# mapleCUx_large_177.net
KiCad netlist of a schematic drawn in EAGLE
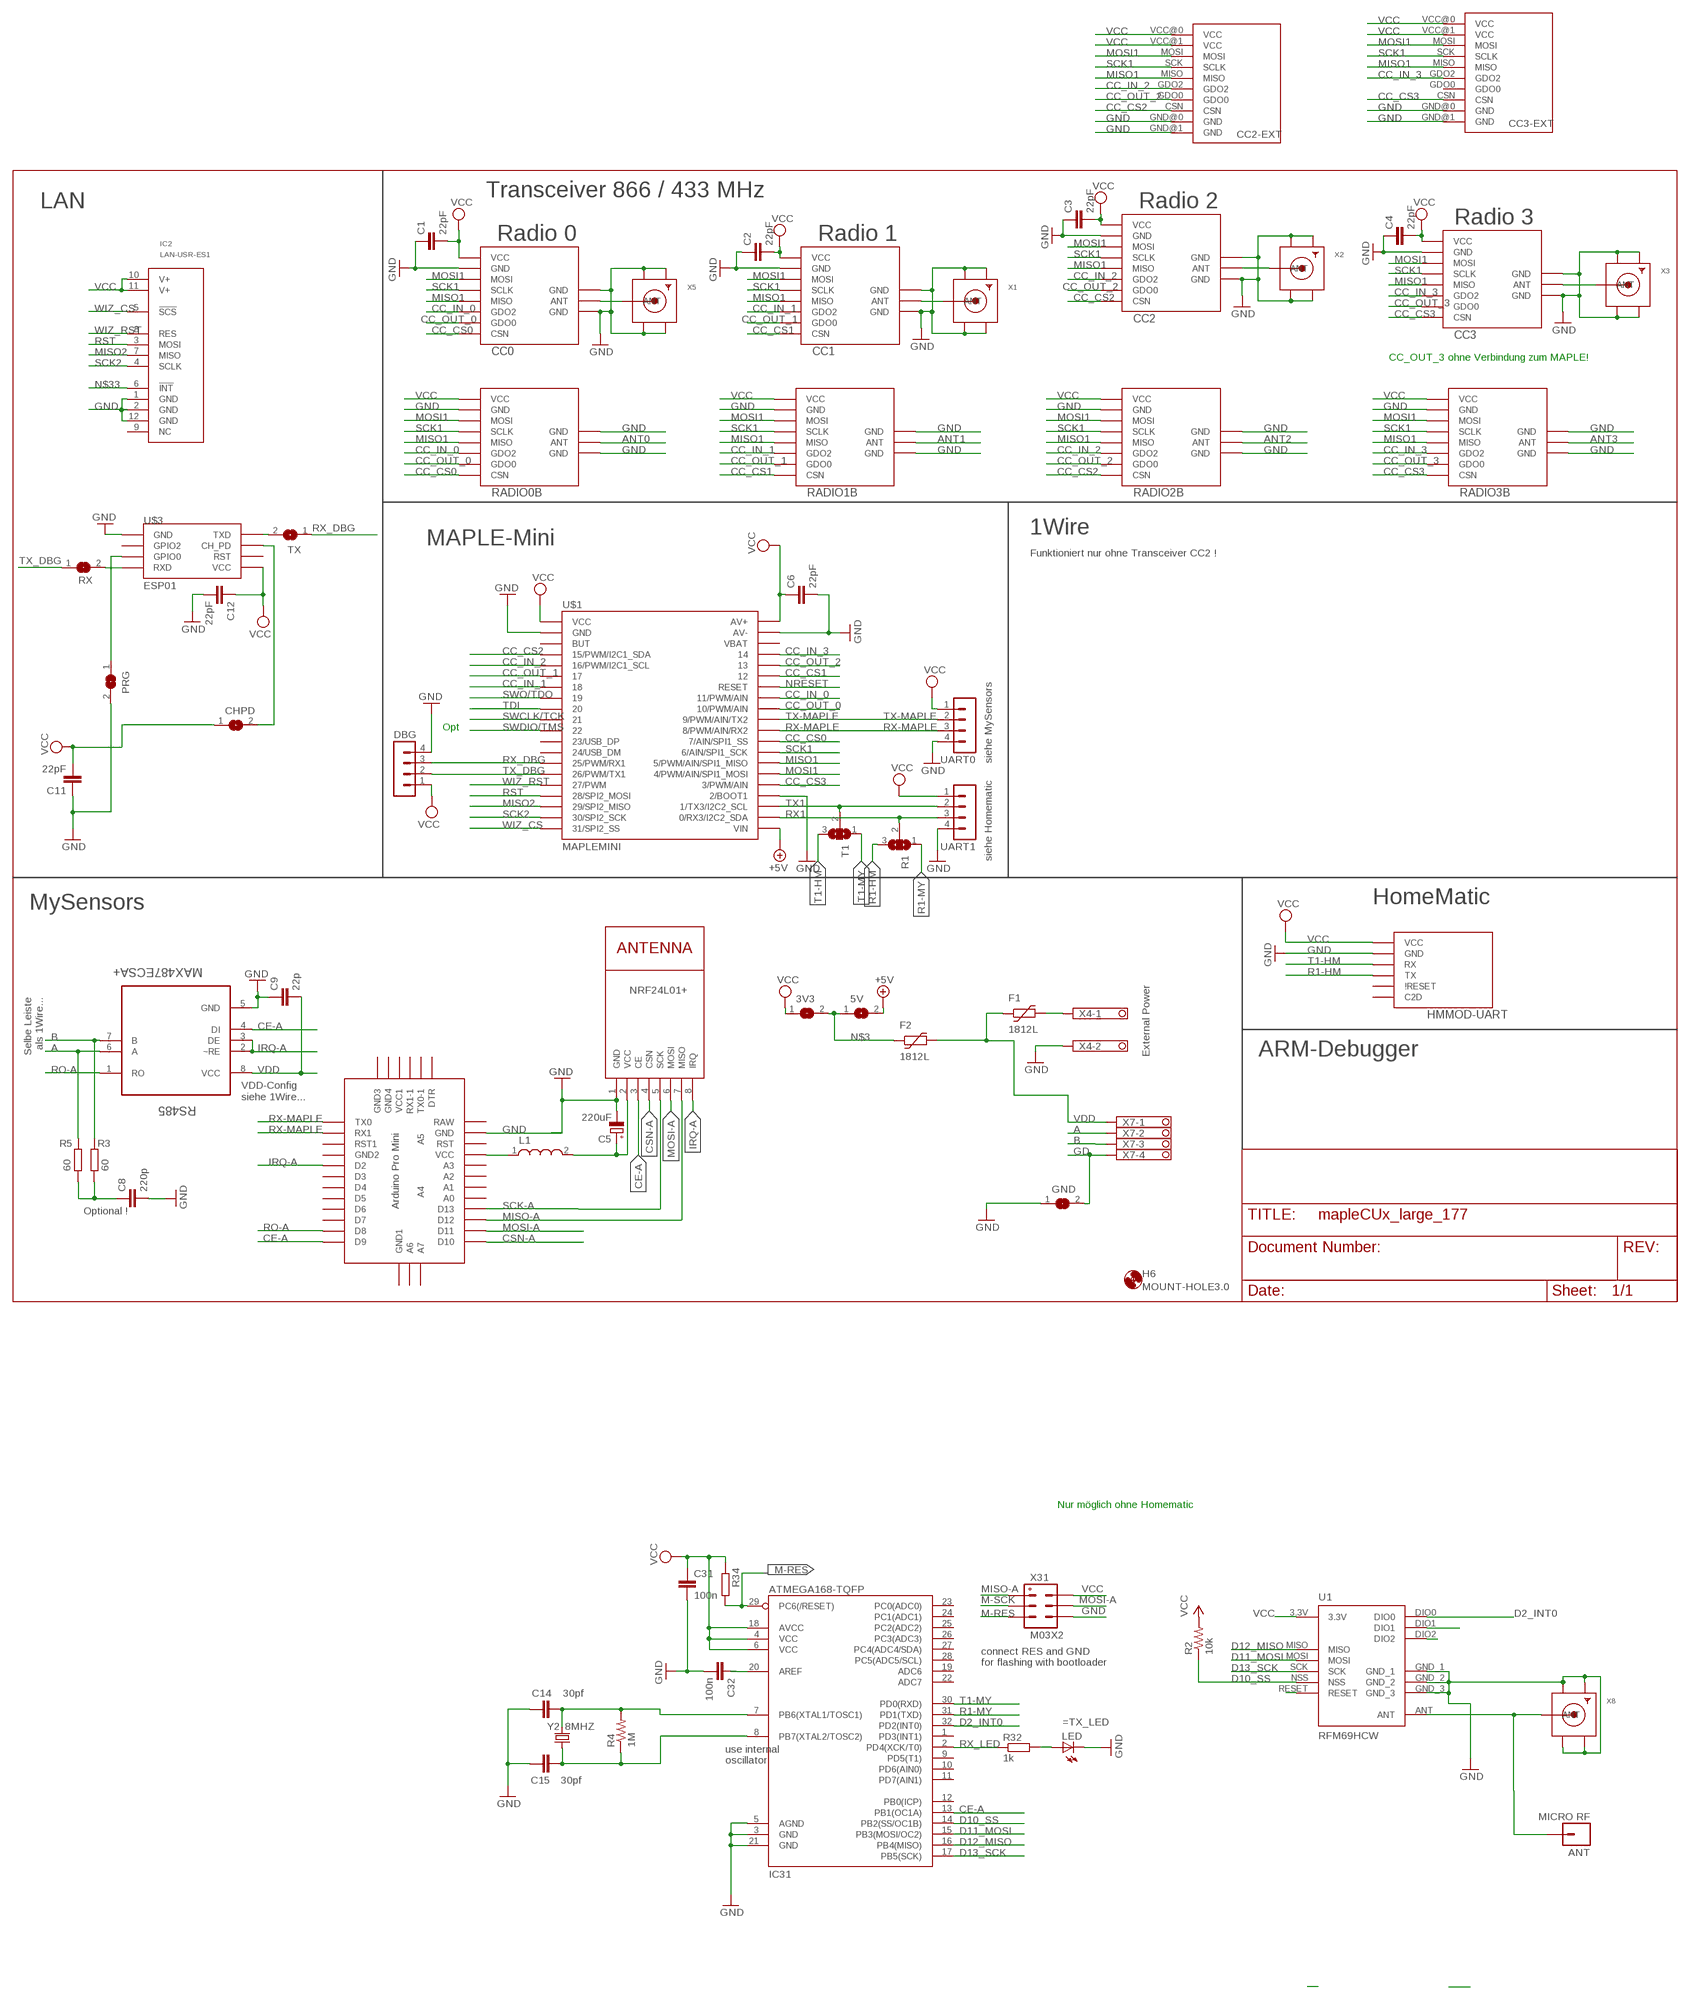
[diagram p0: schematic, sheet 1]

(export (version "E")
  (design (tool "Eeschema 10.0.6"))
  (components
    (comp (ref "3V3") (value "SJ") (footprint "eagle-import:SJ") (libsource (lib "eagle-import") (part "SJ")))
    (comp (ref "5V") (value "SJ") (footprint "eagle-import:SJ") (libsource (lib "eagle-import") (part "SJ")))
    (comp (ref "ANT")
      (value "MICRO RF")
      (footprint "eagle-import:1X01")
      (libsource (lib "eagle-import") (part "M01PTH"))
    )
    (comp (ref "C1")
      (value "22pF")
      (footprint "eagle-import:C0805")
      (libsource (lib "eagle-import") (part "C-EUC0805"))
    )
    (comp (ref "C2")
      (value "22pF")
      (footprint "eagle-import:C0805")
      (libsource (lib "eagle-import") (part "C-EUC0805"))
    )
    (comp (ref "C3")
      (value "22pF")
      (footprint "eagle-import:C0805")
      (libsource (lib "eagle-import") (part "C-EUC0805"))
    )
    (comp (ref "C4")
      (value "22pF")
      (footprint "eagle-import:C0805")
      (libsource (lib "eagle-import") (part "C-EUC0805"))
    )
    (comp (ref "C5")
      (value "220uF")
      (footprint "eagle-import:E5-8,5")
      (libsource (lib "eagle-import") (part "CPOL-EUE5-8.5"))
    )
    (comp (ref "C6")
      (value "22pF")
      (footprint "eagle-import:C0805")
      (libsource (lib "eagle-import") (part "C-EUC0805"))
    )
    (comp (ref "C8")
      (value "220p")
      (footprint "eagle-import:C0805")
      (libsource (lib "eagle-import") (part "C-EUC0805"))
    )
    (comp (ref "C9")
      (value "22p")
      (footprint "eagle-import:C0805")
      (libsource (lib "eagle-import") (part "C-EUC0805"))
    )
    (comp (ref "C11")
      (value "22pF")
      (footprint "eagle-import:C0805")
      (libsource (lib "eagle-import") (part "C-EUC0805"))
    )
    (comp (ref "C12")
      (value "22pF")
      (footprint "eagle-import:C0805")
      (libsource (lib "eagle-import") (part "C-EUC0805"))
    )
    (comp (ref "C14")
      (value "30pf")
      (footprint "eagle-import:0805")
      (libsource (lib "eagle-import") (part "CAP0805"))
    )
    (comp (ref "C15")
      (value "30pf")
      (footprint "eagle-import:0805")
      (libsource (lib "eagle-import") (part "CAP0805"))
    )
    (comp (ref "C31")
      (value "100n")
      (footprint "eagle-import:C0805")
      (libsource (lib "eagle-import") (part "C-EUC0805"))
    )
    (comp (ref "C32")
      (value "100n")
      (footprint "eagle-import:C0805")
      (libsource (lib "eagle-import") (part "C-EUC0805"))
    )
    (comp (ref "CC0")
      (value "CC1101")
      (footprint "eagle-import:CC1101_MODULE1_SMD")
      (libsource (lib "eagle-import") (part "wireless_CC1101_MODULE1SMD"))
    )
    (comp (ref "CC1")
      (value "CC1101_MODULE1SMD")
      (footprint "eagle-import:CC1101_MODULE1_SMD")
      (libsource (lib "eagle-import") (part "wireless_CC1101_MODULE1SMD"))
    )
    (comp (ref "CC2")
      (value "CC1101_MODULE1SMD")
      (footprint "eagle-import:CC1101_MODULE1_SMD")
      (libsource (lib "eagle-import") (part "wireless_CC1101_MODULE1SMD"))
    )
    (comp (ref "CC2-EXT")
      (value "CC1101_MODULE3_DIL")
      (footprint "eagle-import:CC1101_MODULE3_DIL")
      (libsource (lib "eagle-import") (part "CC1101_MODULE3_DIL"))
    )
    (comp (ref "CC3")
      (value "CC1101_MODULE1SMD")
      (footprint "eagle-import:CC1101_MODULE1_SMD")
      (libsource (lib "eagle-import") (part "wireless_CC1101_MODULE1SMD"))
    )
    (comp (ref "CC3-EXT")
      (value "CC1101_MODULE3_DIL")
      (footprint "eagle-import:CC1101_MODULE3_DIL")
      (libsource (lib "eagle-import") (part "CC1101_MODULE3_DIL"))
    )
    (comp (ref "CHPD")
      (value "SJ")
      (footprint "eagle-import:SJ")
      (libsource (lib "eagle-import") (part "SJ"))
    )
    (comp (ref "DBG")
      (value "MA04-1")
      (footprint "eagle-import:MA04-1")
      (libsource (lib "eagle-import") (part "MA04-1"))
    )
    (comp (ref "F1")
      (value "1812L")
      (footprint "eagle-import:1812L")
      (libsource (lib "eagle-import") (part "1812L"))
    )
    (comp (ref "F2")
      (value "1812L")
      (footprint "eagle-import:1812L")
      (libsource (lib "eagle-import") (part "1812L"))
    )
    (comp (ref "GND") (value "SJ") (footprint "eagle-import:SJ") (libsource (lib "eagle-import") (part "SJ")))
    (comp (ref "H6")
      (value "MOUNT-HOLE3.0")
      (footprint "eagle-import:3,0")
      (libsource (lib "eagle-import") (part "MOUNT-HOLE3.0"))
    )
    (comp (ref "HMMOD-UART")
      (value "HM-MOD-UARTDIL")
      (footprint "eagle-import:HM-MOD-UART-DIL")
      (libsource (lib "eagle-import") (part "HM-MOD-UARTDIL"))
    )
    (comp (ref "IC2")
      (value "LAN-USR-ES1")
      (footprint "eagle-import:USR-ES1")
      (libsource (lib "eagle-import") (part "LAN-USR-ES1"))
    )
    (comp (ref "IC31")
      (value "ATMEGA168-TQFP")
      (footprint "eagle-import:TQFP32-08")
      (libsource (lib "eagle-import") (part "ATMEGA168-TQFP"))
    )
    (comp (ref "L1")
      (value "WE-KI_0805A")
      (footprint "eagle-import:WE-KI_0805A")
      (libsource (lib "eagle-import") (part "WE-KI_0805A"))
    )
    (comp (ref "LED")
      (value "LEDCHIPLED_0805")
      (footprint "eagle-import:CHIPLED_0805")
      (libsource (lib "eagle-import") (part "LEDCHIPLED_0805"))
    )
    (comp (ref "NRF24L01+")
      (value "NRF24L01+")
      (footprint "eagle-import:WIRELESS-NRF24L01")
      (libsource (lib "eagle-import") (part "WIRELESS-NRF24L01"))
    )
    (comp (ref "PRG") (value "SJ") (footprint "eagle-import:SJ") (libsource (lib "eagle-import") (part "SJ")))
    (comp (ref "R1")
      (value "SJ2W")
      (footprint "eagle-import:SJ_2")
      (libsource (lib "eagle-import") (part "SJ2W"))
    )
    (comp (ref "R2")
      (value "10k")
      (footprint "eagle-import:0805")
      (libsource (lib "eagle-import") (part "RESISTOR0805-RES"))
    )
    (comp (ref "R3")
      (value "60")
      (footprint "eagle-import:R0805")
      (libsource (lib "eagle-import") (part "R-EU_R0805"))
    )
    (comp (ref "R4")
      (value "1M")
      (footprint "eagle-import:0805")
      (libsource (lib "eagle-import") (part "RESISTOR0805-RES"))
    )
    (comp (ref "R5")
      (value "60")
      (footprint "eagle-import:R0805")
      (libsource (lib "eagle-import") (part "R-EU_R0805"))
    )
    (comp (ref "R32")
      (value "1k")
      (footprint "eagle-import:R0805")
      (libsource (lib "eagle-import") (part "R-EU_R0805"))
    )
    (comp (ref "R34")
      (value "R-EU_R0805")
      (footprint "eagle-import:R0805")
      (libsource (lib "eagle-import") (part "R-EU_R0805"))
    )
    (comp (ref "RADIO0B")
      (value "CC1101_MODULE1SMALL")
      (footprint "eagle-import:CC1101_MODULE1_SMD")
      (libsource (lib "eagle-import") (part "CC1101_MODULE1SMALL"))
    )
    (comp (ref "RADIO1B")
      (value "CC1101_MODULE1SMALL")
      (footprint "eagle-import:CC1101_MODULE1_SMD")
      (libsource (lib "eagle-import") (part "CC1101_MODULE1SMALL"))
    )
    (comp (ref "RADIO2B")
      (value "CC1101_MODULE1SMALL")
      (footprint "eagle-import:CC1101_MODULE1_SMD")
      (libsource (lib "eagle-import") (part "CC1101_MODULE1SMALL"))
    )
    (comp (ref "RADIO3B")
      (value "CC1101_MODULE1SMALL")
      (footprint "eagle-import:CC1101_MODULE1_SMD")
      (libsource (lib "eagle-import") (part "CC1101_MODULE1SMALL"))
    )
    (comp (ref "RS485")
      (value "MAX487ECSA+")
      (footprint "eagle-import:SOIC127P600X175-8N")
      (libsource (lib "eagle-import") (part "MAX487ECSA+"))
    )
    (comp (ref "RX") (value "SJ") (footprint "eagle-import:SJ") (libsource (lib "eagle-import") (part "SJ")))
    (comp (ref "T1")
      (value "SJ2W")
      (footprint "eagle-import:SJ_2")
      (libsource (lib "eagle-import") (part "SJ2W"))
    )
    (comp (ref "TX") (value "SJ") (footprint "eagle-import:SJ") (libsource (lib "eagle-import") (part "SJ")))
    (comp (ref "U$1")
      (value "MAPLEMINI")
      (footprint "eagle-import:20-DIP")
      (libsource (lib "eagle-import") (part "MAPLEMINI"))
    )
    (comp (ref "U$2")
      (value "ABK-PRO-MINI")
      (footprint "eagle-import:ABK-PRO-MINI")
      (libsource (lib "eagle-import") (part "ABK-PRO-MINI"))
    )
    (comp (ref "U$3")
      (value "ESP01")
      (footprint "eagle-import:ESP01")
      (libsource (lib "eagle-import") (part "ESP01"))
    )
    (comp (ref "U1")
      (value "RFM69HCW")
      (footprint "eagle-import:RFM69HCW-XXXS2")
      (libsource (lib "eagle-import") (part "RFM69HCW"))
    )
    (comp (ref "UART0")
      (value "MA04-1")
      (footprint "eagle-import:MA04-1")
      (libsource (lib "eagle-import") (part "MA04-1"))
    )
    (comp (ref "UART1")
      (value "MA04-1")
      (footprint "eagle-import:MA04-1")
      (libsource (lib "eagle-import") (part "MA04-1"))
    )
    (comp (ref "X1")
      (value "SMACONNECTOR_EDGE_UFL")
      (footprint "eagle-import:SMA_EDGELAUNCH_UFL")
      (libsource (lib "eagle-import") (part "SMACONNECTOR_EDGE_UFL"))
    )
    (comp (ref "X2")
      (value "SMACONNECTOR_EDGE_UFL")
      (footprint "eagle-import:SMA_EDGELAUNCH_UFL")
      (libsource (lib "eagle-import") (part "SMACONNECTOR_EDGE_UFL"))
    )
    (comp (ref "X3")
      (value "SMACONNECTOR_EDGE_UFL")
      (footprint "eagle-import:SMA_EDGELAUNCH_UFL")
      (libsource (lib "eagle-import") (part "SMACONNECTOR_EDGE_UFL"))
    )
    (comp (ref "X4")
      (value "1751248")
      (footprint "eagle-import:1751248")
      (libsource (lib "eagle-import") (part "1751248"))
    )
    (comp (ref "X5")
      (value "SMACONNECTOR_EDGE_UFL")
      (footprint "eagle-import:SMA_EDGELAUNCH_UFL")
      (libsource (lib "eagle-import") (part "SMACONNECTOR_EDGE_UFL"))
    )
    (comp (ref "X7")
      (value "1751264")
      (footprint "eagle-import:1751264")
      (libsource (lib "eagle-import") (part "1751264"))
    )
    (comp (ref "X8")
      (value "SMACONNECTOR_EDGE_UFL")
      (footprint "eagle-import:SMA_EDGELAUNCH_UFL")
      (libsource (lib "eagle-import") (part "SMACONNECTOR_EDGE_UFL"))
    )
    (comp (ref "X31")
      (value "M03X2")
      (footprint "eagle-import:2X03-1.27MM_SMD")
      (libsource (lib "eagle-import") (part "M03X2"))
    )
    (comp (ref "Y2")
      (value "8MHZ")
      (footprint "eagle-import:CRYSTAL-TXC-7A")
      (libsource (lib "eagle-import") (part "CRYSTALTXC-7A"))
    )
  )
  (nets
    (net (code "1") (name "+5V") (class "Default")
      (node (ref "5V") (pin "2") (pinfunction "2_2") (pintype "passive"))
      (node (ref "U$1") (pin "21") (pinfunction "VIN_21") (pintype "bidirectional"))
    )
    (net (code "2") (name "/A") (class "Default")
      (node (ref "R5") (pin "2") (pinfunction "2_2") (pintype "passive"))
      (node (ref "RS485") (pin "6") (pinfunction "A_6") (pintype "bidirectional"))
      (node (ref "X7") (pin "2") (pinfunction "K_2") (pintype "passive"))
    )
    (net (code "3") (name "/ANT0") (class "Default")
      (node (ref "CC0") (pin "ANT") (pinfunction "ANT_ANT") (pintype "output"))
      (node (ref "RADIO0B") (pin "ANT") (pinfunction "ANT_ANT") (pintype "output"))
      (node (ref "X5") (pin "P") (pinfunction "ANT_P") (pintype "bidirectional"))
    )
    (net (code "4") (name "/ANT1") (class "Default")
      (node (ref "CC1") (pin "ANT") (pinfunction "ANT_ANT") (pintype "output"))
      (node (ref "RADIO1B") (pin "ANT") (pinfunction "ANT_ANT") (pintype "output"))
      (node (ref "X1") (pin "P") (pinfunction "ANT_P") (pintype "bidirectional"))
    )
    (net (code "5") (name "/ANT2") (class "Default")
      (node (ref "CC2") (pin "ANT") (pinfunction "ANT_ANT") (pintype "output"))
      (node (ref "RADIO2B") (pin "ANT") (pinfunction "ANT_ANT") (pintype "output"))
      (node (ref "X2") (pin "P") (pinfunction "ANT_P") (pintype "bidirectional"))
    )
    (net (code "6") (name "/ANT3") (class "Default")
      (node (ref "CC3") (pin "ANT") (pinfunction "ANT_ANT") (pintype "output"))
      (node (ref "RADIO3B") (pin "ANT") (pinfunction "ANT_ANT") (pintype "output"))
      (node (ref "X3") (pin "P") (pinfunction "ANT_P") (pintype "bidirectional"))
    )
    (net (code "7") (name "/B") (class "Default")
      (node (ref "R3") (pin "2") (pinfunction "2_2") (pintype "passive"))
      (node (ref "RS485") (pin "7") (pinfunction "B_7") (pintype "bidirectional"))
      (node (ref "X7") (pin "3") (pinfunction "K_3") (pintype "passive"))
    )
    (net (code "8") (name "/CC_CS0") (class "Default")
      (node (ref "CC0") (pin "CSN") (pinfunction "CSN_CSN") (pintype "bidirectional"))
      (node (ref "RADIO0B") (pin "CSN") (pinfunction "CSN_CSN") (pintype "bidirectional"))
      (node (ref "U$1") (pin "29") (pinfunction "7/AIN/SPI1_SS_29") (pintype "bidirectional"))
    )
    (net (code "9") (name "/CC_CS1") (class "Default")
      (node (ref "CC1") (pin "CSN") (pinfunction "CSN_CSN") (pintype "bidirectional"))
      (node (ref "RADIO1B") (pin "CSN") (pinfunction "CSN_CSN") (pintype "bidirectional"))
      (node (ref "U$1") (pin "35") (pinfunction "12_35") (pintype "bidirectional"))
    )
    (net (code "10") (name "/CC_CS2") (class "Default")
      (node (ref "CC2") (pin "CSN") (pinfunction "CSN_CSN") (pintype "bidirectional"))
      (node (ref "CC2-EXT") (pin "CSN") (pinfunction "CSN_CSN") (pintype "bidirectional"))
      (node (ref "RADIO2B") (pin "CSN") (pinfunction "CSN_CSN") (pintype "bidirectional"))
      (node (ref "U$1") (pin "4") (pinfunction "15/PWM/I2C1_SDA_4") (pintype "bidirectional"))
    )
    (net (code "11") (name "/CC_CS3") (class "Default")
      (node (ref "CC3") (pin "CSN") (pinfunction "CSN_CSN") (pintype "bidirectional"))
      (node (ref "CC3-EXT") (pin "CSN") (pinfunction "CSN_CSN") (pintype "bidirectional"))
      (node (ref "RADIO3B") (pin "CSN") (pinfunction "CSN_CSN") (pintype "bidirectional"))
      (node (ref "U$1") (pin "25") (pinfunction "3/PWM/AIN_25") (pintype "bidirectional"))
    )
    (net (code "12") (name "/CC_IN_0") (class "Default")
      (node (ref "CC0") (pin "GDO2") (pinfunction "GDO2_GDO2") (pintype "bidirectional"))
      (node (ref "RADIO0B") (pin "GDO2") (pinfunction "GDO2_GDO2") (pintype "bidirectional"))
      (node (ref "U$1") (pin "33") (pinfunction "11/PWM/AIN_33") (pintype "bidirectional"))
    )
    (net (code "13") (name "/CC_IN_1") (class "Default")
      (node (ref "CC1") (pin "GDO2") (pinfunction "GDO2_GDO2") (pintype "bidirectional"))
      (node (ref "RADIO1B") (pin "GDO2") (pinfunction "GDO2_GDO2") (pintype "bidirectional"))
      (node (ref "U$1") (pin "7") (pinfunction "18_7") (pintype "bidirectional"))
    )
    (net (code "14") (name "/CC_IN_2") (class "Default")
      (node (ref "CC2") (pin "GDO2") (pinfunction "GDO2_GDO2") (pintype "bidirectional"))
      (node (ref "CC2-EXT") (pin "GDO2") (pinfunction "GDO2_GDO2") (pintype "bidirectional"))
      (node (ref "RADIO2B") (pin "GDO2") (pinfunction "GDO2_GDO2") (pintype "bidirectional"))
      (node (ref "U$1") (pin "5") (pinfunction "16/PWM/I2C1_SCL_5") (pintype "bidirectional"))
    )
    (net (code "15") (name "/CC_IN_3") (class "Default")
      (node (ref "CC3") (pin "GDO2") (pinfunction "GDO2_GDO2") (pintype "bidirectional"))
      (node (ref "CC3-EXT") (pin "GDO2") (pinfunction "GDO2_GDO2") (pintype "bidirectional"))
      (node (ref "RADIO3B") (pin "GDO2") (pinfunction "GDO2_GDO2") (pintype "bidirectional"))
      (node (ref "U$1") (pin "37") (pinfunction "14_37") (pintype "bidirectional"))
    )
    (net (code "16") (name "/CC_OUT_0") (class "Default")
      (node (ref "CC0") (pin "GDO0") (pinfunction "GDO0_GDO0") (pintype "bidirectional"))
      (node (ref "RADIO0B") (pin "GDO0") (pinfunction "GDO0_GDO0") (pintype "bidirectional"))
      (node (ref "U$1") (pin "32") (pinfunction "10/PWM/AIN_32") (pintype "bidirectional"))
    )
    (net (code "17") (name "/CC_OUT_1") (class "Default")
      (node (ref "CC1") (pin "GDO0") (pinfunction "GDO0_GDO0") (pintype "bidirectional"))
      (node (ref "RADIO1B") (pin "GDO0") (pinfunction "GDO0_GDO0") (pintype "bidirectional"))
      (node (ref "U$1") (pin "6") (pinfunction "17_6") (pintype "bidirectional"))
    )
    (net (code "18") (name "/CC_OUT_2") (class "Default")
      (node (ref "CC2") (pin "GDO0") (pinfunction "GDO0_GDO0") (pintype "bidirectional"))
      (node (ref "CC2-EXT") (pin "GDO0") (pinfunction "GDO0_GDO0") (pintype "bidirectional"))
      (node (ref "RADIO2B") (pin "GDO0") (pinfunction "GDO0_GDO0") (pintype "bidirectional"))
      (node (ref "U$1") (pin "36") (pinfunction "13_36") (pintype "bidirectional"))
    )
    (net (code "19") (name "/CC_OUT_3") (class "Default")
      (node (ref "CC3") (pin "GDO0") (pinfunction "GDO0_GDO0") (pintype "bidirectional"))
      (node (ref "RADIO3B") (pin "GDO0") (pinfunction "GDO0_GDO0") (pintype "bidirectional"))
    )
    (net (code "20") (name "/D2_INT0") (class "Default")
      (node (ref "IC31") (pin "32") (pinfunction "PD2(INT0)_32") (pintype "bidirectional"))
      (node (ref "U1") (pin "DIO0") (pinfunction "DIO0_DIO0") (pintype "bidirectional"))
    )
    (net (code "21") (name "/D10_SS") (class "Default")
      (node (ref "IC31") (pin "14") (pinfunction "PB2(SS/OC1B)_14") (pintype "bidirectional"))
      (node (ref "R2") (pin "1") (pinfunction "1_1") (pintype "passive"))
      (node (ref "U1") (pin "NSS") (pinfunction "NSS_NSS") (pintype "input"))
    )
    (net (code "22") (name "/D11_MOSI") (class "Default")
      (node (ref "IC31") (pin "15") (pinfunction "PB3(MOSI/OC2)_15") (pintype "bidirectional"))
      (node (ref "U1") (pin "MOSI") (pinfunction "MOSI_MOSI") (pintype "input"))
    )
    (net (code "23") (name "/D12_MISO") (class "Default")
      (node (ref "IC31") (pin "16") (pinfunction "PB4(MISO)_16") (pintype "bidirectional"))
      (node (ref "U1") (pin "MISO") (pinfunction "MISO_MISO") (pintype "bidirectional"))
    )
    (net (code "24") (name "/D13_SCK") (class "Default")
      (node (ref "IC31") (pin "17") (pinfunction "PB5(SCK)_17") (pintype "bidirectional"))
      (node (ref "U1") (pin "SCK") (pinfunction "SCK_SCK") (pintype "input"))
    )
    (net (code "25") (name "/GD") (class "Default")
      (node (ref "GND") (pin "2") (pinfunction "2_2") (pintype "passive"))
      (node (ref "X7") (pin "4") (pinfunction "K_4") (pintype "passive"))
    )
    (net (code "26") (name "/M-RES") (class "Default")
      (node (ref "IC31") (pin "29") (pinfunction "PC6(/RESET)_29") (pintype "bidirectional"))
      (node (ref "R34") (pin "2") (pinfunction "2_2") (pintype "passive"))
      (node (ref "X31") (pin "P$5") (pinfunction "5_P$5") (pintype "passive"))
    )
    (net (code "27") (name "/M-SCK") (class "Default")
      (node (ref "X31") (pin "P$3") (pinfunction "3_P$3") (pintype "passive"))
    )
    (net (code "28") (name "/MISO-A") (class "Default")
      (node (ref "NRF24L01+") (pin "7") (pinfunction "MISO_7") (pintype "bidirectional"))
      (node (ref "U$2") (pin "D12") (pinfunction "D12_D12") (pintype "bidirectional"))
      (node (ref "X31") (pin "P$1") (pinfunction "1_P$1") (pintype "passive"))
    )
    (net (code "29") (name "/MISO1") (class "Default")
      (node (ref "CC0") (pin "MISO") (pinfunction "MISO_MISO") (pintype "bidirectional"))
      (node (ref "CC1") (pin "MISO") (pinfunction "MISO_MISO") (pintype "bidirectional"))
      (node (ref "CC2") (pin "MISO") (pinfunction "MISO_MISO") (pintype "bidirectional"))
      (node (ref "CC2-EXT") (pin "MISO") (pinfunction "MISO_MISO") (pintype "bidirectional"))
      (node (ref "CC3") (pin "MISO") (pinfunction "MISO_MISO") (pintype "bidirectional"))
      (node (ref "CC3-EXT") (pin "MISO") (pinfunction "MISO_MISO") (pintype "bidirectional"))
      (node (ref "RADIO0B") (pin "MISO") (pinfunction "MISO_MISO") (pintype "bidirectional"))
      (node (ref "RADIO1B") (pin "MISO") (pinfunction "MISO_MISO") (pintype "bidirectional"))
      (node (ref "RADIO2B") (pin "MISO") (pinfunction "MISO_MISO") (pintype "bidirectional"))
      (node (ref "RADIO3B") (pin "MISO") (pinfunction "MISO_MISO") (pintype "bidirectional"))
      (node (ref "U$1") (pin "27") (pinfunction "5/PWM/AIN/SPI1_MISO_27") (pintype "bidirectional"))
    )
    (net (code "30") (name "/MISO2") (class "Default")
      (node (ref "IC2") (pin "7") (pinfunction "MISO_7") (pintype "bidirectional"))
      (node (ref "U$1") (pin "18") (pinfunction "29/SPI2_MISO_18") (pintype "bidirectional"))
    )
    (net (code "31") (name "/MOSI1") (class "Default")
      (node (ref "CC0") (pin "MOSI") (pinfunction "MOSI_MOSI") (pintype "bidirectional"))
      (node (ref "CC1") (pin "MOSI") (pinfunction "MOSI_MOSI") (pintype "bidirectional"))
      (node (ref "CC2") (pin "MOSI") (pinfunction "MOSI_MOSI") (pintype "bidirectional"))
      (node (ref "CC2-EXT") (pin "MOSI") (pinfunction "MOSI_MOSI") (pintype "bidirectional"))
      (node (ref "CC3") (pin "MOSI") (pinfunction "MOSI_MOSI") (pintype "bidirectional"))
      (node (ref "CC3-EXT") (pin "MOSI") (pinfunction "MOSI_MOSI") (pintype "bidirectional"))
      (node (ref "RADIO0B") (pin "MOSI") (pinfunction "MOSI_MOSI") (pintype "bidirectional"))
      (node (ref "RADIO1B") (pin "MOSI") (pinfunction "MOSI_MOSI") (pintype "bidirectional"))
      (node (ref "RADIO2B") (pin "MOSI") (pinfunction "MOSI_MOSI") (pintype "bidirectional"))
      (node (ref "RADIO3B") (pin "MOSI") (pinfunction "MOSI_MOSI") (pintype "bidirectional"))
      (node (ref "U$1") (pin "26") (pinfunction "4/PWM/AIN/SPI1_MOSI_26") (pintype "bidirectional"))
    )
    (net (code "32") (name "/N$3") (class "Default")
      (node (ref "3V3") (pin "2") (pinfunction "2_2") (pintype "passive"))
      (node (ref "5V") (pin "1") (pinfunction "1_1") (pintype "passive"))
      (node (ref "F2") (pin "P$1") (pinfunction "1_P$1") (pintype "passive"))
    )
    (net (code "33") (name "/N$33") (class "Default")
      (node (ref "IC2") (pin "6") (pinfunction "~{INT}_6") (pintype "output"))
    )
    (net (code "34") (name "/NRESET") (class "Default")
      (node (ref "U$1") (pin "34") (pinfunction "RESET_34") (pintype "bidirectional"))
    )
    (net (code "35") (name "/RO-A") (class "Default")
      (node (ref "RS485") (pin "1") (pinfunction "RO_1") (pintype "output"))
      (node (ref "U$2") (pin "D8") (pinfunction "D8_D8") (pintype "bidirectional"))
    )
    (net (code "36") (name "/RST") (class "Default")
      (node (ref "IC2") (pin "3") (pinfunction "MOSI_3") (pintype "bidirectional"))
      (node (ref "U$1") (pin "17") (pinfunction "28/SPI2_MOSI_17") (pintype "bidirectional"))
    )
    (net (code "37") (name "/RX-MAPLE") (class "Default")
      (node (ref "U$1") (pin "30") (pinfunction "8/PWM/AIN/RX2_30") (pintype "bidirectional"))
      (node (ref "U$2") (pin "RX1") (pinfunction "RX1_RX1") (pintype "bidirectional"))
      (node (ref "U$2") (pin "TX0") (pinfunction "TX0_TX0") (pintype "bidirectional"))
      (node (ref "UART0") (pin "3") (pinfunction "3_3") (pintype "passive"))
    )
    (net (code "38") (name "/RX1") (class "Default")
      (node (ref "R1") (pin "2") (pinfunction "2_2") (pintype "passive"))
      (node (ref "U$1") (pin "22") (pinfunction "0/RX3/I2C2_SDA_22") (pintype "bidirectional"))
      (node (ref "UART1") (pin "3") (pinfunction "3_3") (pintype "passive"))
    )
    (net (code "39") (name "/RX_DBG") (class "Default")
      (node (ref "DBG") (pin "3") (pinfunction "3_3") (pintype "passive"))
      (node (ref "TX") (pin "1") (pinfunction "1_1") (pintype "passive"))
      (node (ref "U$1") (pin "14") (pinfunction "25/PWM/RX1_14") (pintype "bidirectional"))
    )
    (net (code "40") (name "/RX_LED") (class "Default")
      (node (ref "IC31") (pin "2") (pinfunction "PD4(XCK/T0)_2") (pintype "bidirectional"))
      (node (ref "R32") (pin "1") (pinfunction "1_1") (pintype "passive"))
    )
    (net (code "41") (name "/SCK-A") (class "Default")
      (node (ref "NRF24L01+") (pin "5") (pinfunction "SCK_5") (pintype "bidirectional"))
      (node (ref "U$2") (pin "D13") (pinfunction "D13_D13") (pintype "bidirectional"))
    )
    (net (code "42") (name "/SCK1") (class "Default")
      (node (ref "CC0") (pin "SCLK") (pinfunction "SCLK_SCLK") (pintype "bidirectional"))
      (node (ref "CC1") (pin "SCLK") (pinfunction "SCLK_SCLK") (pintype "bidirectional"))
      (node (ref "CC2") (pin "SCLK") (pinfunction "SCLK_SCLK") (pintype "bidirectional"))
      (node (ref "CC2-EXT") (pin "SCK") (pinfunction "SCLK_SCK") (pintype "bidirectional"))
      (node (ref "CC3") (pin "SCLK") (pinfunction "SCLK_SCLK") (pintype "bidirectional"))
      (node (ref "CC3-EXT") (pin "SCK") (pinfunction "SCLK_SCK") (pintype "bidirectional"))
      (node (ref "RADIO0B") (pin "SCLK") (pinfunction "SCLK_SCLK") (pintype "bidirectional"))
      (node (ref "RADIO1B") (pin "SCLK") (pinfunction "SCLK_SCLK") (pintype "bidirectional"))
      (node (ref "RADIO2B") (pin "SCLK") (pinfunction "SCLK_SCLK") (pintype "bidirectional"))
      (node (ref "RADIO3B") (pin "SCLK") (pinfunction "SCLK_SCLK") (pintype "bidirectional"))
      (node (ref "U$1") (pin "28") (pinfunction "6/AIN/SPI1_SCK_28") (pintype "bidirectional"))
    )
    (net (code "43") (name "/SCK2") (class "Default")
      (node (ref "IC2") (pin "4") (pinfunction "SCLK_4") (pintype "input"))
      (node (ref "U$1") (pin "19") (pinfunction "30/SPI2_SCK_19") (pintype "bidirectional"))
    )
    (net (code "44") (name "/SWCLK{slash}TCK") (class "Default")
      (node (ref "U$1") (pin "10") (pinfunction "21_10") (pintype "bidirectional"))
    )
    (net (code "45") (name "/SWDIO{slash}TMS") (class "Default")
      (node (ref "U$1") (pin "11") (pinfunction "22_11") (pintype "bidirectional"))
    )
    (net (code "46") (name "/SWO{slash}TDO") (class "Default")
      (node (ref "U$1") (pin "8") (pinfunction "19_8") (pintype "bidirectional"))
    )
    (net (code "47") (name "/TDI") (class "Default")
      (node (ref "U$1") (pin "9") (pinfunction "20_9") (pintype "bidirectional"))
    )
    (net (code "48") (name "/TX-MAPLE") (class "Default")
      (node (ref "U$1") (pin "31") (pinfunction "9/PWM/AIN/TX2_31") (pintype "bidirectional"))
      (node (ref "UART0") (pin "2") (pinfunction "2_2") (pintype "passive"))
    )
    (net (code "49") (name "/TX1") (class "Default")
      (node (ref "T1") (pin "2") (pinfunction "2_2") (pintype "passive"))
      (node (ref "U$1") (pin "23") (pinfunction "1/TX3/I2C2_SCL_23") (pintype "bidirectional"))
      (node (ref "UART1") (pin "2") (pinfunction "2_2") (pintype "passive"))
    )
    (net (code "50") (name "/TX_DBG") (class "Default")
      (node (ref "DBG") (pin "2") (pinfunction "2_2") (pintype "passive"))
      (node (ref "RX") (pin "1") (pinfunction "1_1") (pintype "passive"))
      (node (ref "U$1") (pin "15") (pinfunction "26/PWM/TX1_15") (pintype "bidirectional"))
    )
    (net (code "51") (name "/VDD") (class "Default")
      (node (ref "C9") (pin "2") (pinfunction "2_2") (pintype "passive"))
      (node (ref "F1") (pin "P$1") (pinfunction "1_P$1") (pintype "passive"))
      (node (ref "F2") (pin "P$2") (pinfunction "2_P$2") (pintype "passive"))
      (node (ref "RS485") (pin "8") (pinfunction "VCC_8") (pintype "power_in"))
      (node (ref "X7") (pin "1") (pinfunction "K_1") (pintype "passive"))
    )
    (net (code "52") (name "/WIZ_CS") (class "Default")
      (node (ref "IC2") (pin "5") (pinfunction "~{SCS}_5") (pintype "input"))
      (node (ref "U$1") (pin "20") (pinfunction "31/SPI2_SS_20") (pintype "bidirectional"))
    )
    (net (code "53") (name "/WIZ_RST") (class "Default")
      (node (ref "IC2") (pin "8") (pinfunction "RES_8") (pintype "input"))
      (node (ref "U$1") (pin "16") (pinfunction "27/PWM_16") (pintype "bidirectional"))
    )
    (net (code "54") (name "CE-A") (class "Default")
      (node (ref "IC31") (pin "13") (pinfunction "PB1(OC1A)_13") (pintype "bidirectional"))
      (node (ref "NRF24L01+") (pin "3") (pinfunction "CE_3") (pintype "bidirectional"))
      (node (ref "RS485") (pin "4") (pinfunction "DI_4") (pintype "input"))
      (node (ref "U$2") (pin "D9") (pinfunction "D9_D9") (pintype "bidirectional"))
    )
    (net (code "55") (name "CSN-A") (class "Default")
      (node (ref "NRF24L01+") (pin "4") (pinfunction "CSN_4") (pintype "bidirectional"))
      (node (ref "U$2") (pin "D10") (pinfunction "D10_D10") (pintype "bidirectional"))
    )
    (net (code "56") (name "GND") (class "Default")
      (node (ref "C1") (pin "1") (pinfunction "1_1") (pintype "passive"))
      (node (ref "C11") (pin "1") (pinfunction "1_1") (pintype "passive"))
      (node (ref "C12") (pin "2") (pinfunction "2_2") (pintype "passive"))
      (node (ref "C14") (pin "1") (pinfunction "1_1") (pintype "passive"))
      (node (ref "C15") (pin "1") (pinfunction "1_1") (pintype "passive"))
      (node (ref "C2") (pin "1") (pinfunction "1_1") (pintype "passive"))
      (node (ref "C3") (pin "1") (pinfunction "1_1") (pintype "passive"))
      (node (ref "C31") (pin "2") (pinfunction "2_2") (pintype "passive"))
      (node (ref "C32") (pin "2") (pinfunction "2_2") (pintype "passive"))
      (node (ref "C4") (pin "1") (pinfunction "1_1") (pintype "passive"))
      (node (ref "C5") (pin "-") (pinfunction "-_-") (pintype "passive"))
      (node (ref "C6") (pin "2") (pinfunction "2_2") (pintype "passive"))
      (node (ref "C8") (pin "2") (pinfunction "2_2") (pintype "passive"))
      (node (ref "C9") (pin "1") (pinfunction "1_1") (pintype "passive"))
      (node (ref "CC0") (pin "GND@0") (pinfunction "GND_GND@0") (pintype "power_in"))
      (node (ref "CC0") (pin "GND@1") (pinfunction "GND_GND@1") (pintype "power_in"))
      (node (ref "CC0") (pin "GND@2") (pinfunction "GND_GND@2") (pintype "power_in"))
      (node (ref "CC1") (pin "GND@0") (pinfunction "GND_GND@0") (pintype "power_in"))
      (node (ref "CC1") (pin "GND@1") (pinfunction "GND_GND@1") (pintype "power_in"))
      (node (ref "CC1") (pin "GND@2") (pinfunction "GND_GND@2") (pintype "power_in"))
      (node (ref "CC2") (pin "GND@0") (pinfunction "GND_GND@0") (pintype "power_in"))
      (node (ref "CC2") (pin "GND@1") (pinfunction "GND_GND@1") (pintype "power_in"))
      (node (ref "CC2") (pin "GND@2") (pinfunction "GND_GND@2") (pintype "power_in"))
      (node (ref "CC2-EXT") (pin "GND@0") (pinfunction "GND_GND@0") (pintype "power_in"))
      (node (ref "CC2-EXT") (pin "GND@1") (pinfunction "GND_GND@1") (pintype "power_in"))
      (node (ref "CC3") (pin "GND@0") (pinfunction "GND_GND@0") (pintype "power_in"))
      (node (ref "CC3") (pin "GND@1") (pinfunction "GND_GND@1") (pintype "power_in"))
      (node (ref "CC3") (pin "GND@2") (pinfunction "GND_GND@2") (pintype "power_in"))
      (node (ref "CC3-EXT") (pin "GND@0") (pinfunction "GND_GND@0") (pintype "power_in"))
      (node (ref "CC3-EXT") (pin "GND@1") (pinfunction "GND_GND@1") (pintype "power_in"))
      (node (ref "DBG") (pin "4") (pinfunction "4_4") (pintype "passive"))
      (node (ref "GND") (pin "1") (pinfunction "1_1") (pintype "passive"))
      (node (ref "HMMOD-UART") (pin "2") (pinfunction "GND_2") (pintype "power_in"))
      (node (ref "IC2") (pin "1") (pinfunction "GND_1") (pintype "power_in"))
      (node (ref "IC2") (pin "12") (pinfunction "GND_12") (pintype "power_in"))
      (node (ref "IC2") (pin "2") (pinfunction "GND_2") (pintype "power_in"))
      (node (ref "IC31") (pin "21") (pinfunction "GND_21") (pintype "bidirectional"))
      (node (ref "IC31") (pin "3") (pinfunction "GND_3") (pintype "bidirectional"))
      (node (ref "IC31") (pin "5") (pinfunction "AGND_5") (pintype "bidirectional"))
      (node (ref "LED") (pin "C") (pinfunction "C_C") (pintype "passive"))
      (node (ref "NRF24L01+") (pin "1") (pinfunction "GND_1") (pintype "power_in"))
      (node (ref "PRG") (pin "2") (pinfunction "2_2") (pintype "passive"))
      (node (ref "RADIO0B") (pin "GND@0") (pinfunction "GND_GND@0") (pintype "power_in"))
      (node (ref "RADIO0B") (pin "GND@1") (pinfunction "GND_GND@1") (pintype "power_in"))
      (node (ref "RADIO0B") (pin "GND@2") (pinfunction "GND_GND@2") (pintype "power_in"))
      (node (ref "RADIO1B") (pin "GND@0") (pinfunction "GND_GND@0") (pintype "power_in"))
      (node (ref "RADIO1B") (pin "GND@1") (pinfunction "GND_GND@1") (pintype "power_in"))
      (node (ref "RADIO1B") (pin "GND@2") (pinfunction "GND_GND@2") (pintype "power_in"))
      (node (ref "RADIO2B") (pin "GND@0") (pinfunction "GND_GND@0") (pintype "power_in"))
      (node (ref "RADIO2B") (pin "GND@1") (pinfunction "GND_GND@1") (pintype "power_in"))
      (node (ref "RADIO2B") (pin "GND@2") (pinfunction "GND_GND@2") (pintype "power_in"))
      (node (ref "RADIO3B") (pin "GND@0") (pinfunction "GND_GND@0") (pintype "power_in"))
      (node (ref "RADIO3B") (pin "GND@1") (pinfunction "GND_GND@1") (pintype "power_in"))
      (node (ref "RADIO3B") (pin "GND@2") (pinfunction "GND_GND@2") (pintype "power_in"))
      (node (ref "RS485") (pin "5") (pinfunction "GND_5") (pintype "passive"))
      (node (ref "U$1") (pin "2") (pinfunction "GND_2") (pintype "bidirectional"))
      (node (ref "U$1") (pin "24") (pinfunction "2/BOOT1_24") (pintype "bidirectional"))
      (node (ref "U$1") (pin "39") (pinfunction "AV-_39") (pintype "bidirectional"))
      (node (ref "U$2") (pin "GND") (pinfunction "GND_GND") (pintype "bidirectional"))
      (node (ref "U$3") (pin "GND") (pinfunction "GND_GND") (pintype "bidirectional"))
      (node (ref "U1") (pin "GND_1") (pinfunction "GND_1_GND_1") (pintype "power_in"))
      (node (ref "U1") (pin "GND_2") (pinfunction "GND_2_GND_2") (pintype "power_in"))
      (node (ref "U1") (pin "GND_3") (pinfunction "GND_3_GND_3") (pintype "power_in"))
      (node (ref "UART0") (pin "4") (pinfunction "4_4") (pintype "passive"))
      (node (ref "UART1") (pin "4") (pinfunction "4_4") (pintype "passive"))
      (node (ref "X1") (pin "GND@1") (pinfunction "GND1_GND@1") (pintype "power_in"))
      (node (ref "X1") (pin "GND@2") (pinfunction "GND2_GND@2") (pintype "power_in"))
      (node (ref "X1") (pin "GND@3") (pinfunction "GND3_GND@3") (pintype "power_in"))
      (node (ref "X1") (pin "GND@4") (pinfunction "GND4_GND@4") (pintype "power_in"))
      (node (ref "X2") (pin "GND@1") (pinfunction "GND1_GND@1") (pintype "power_in"))
      (node (ref "X2") (pin "GND@2") (pinfunction "GND2_GND@2") (pintype "power_in"))
      (node (ref "X2") (pin "GND@3") (pinfunction "GND3_GND@3") (pintype "power_in"))
      (node (ref "X2") (pin "GND@4") (pinfunction "GND4_GND@4") (pintype "power_in"))
      (node (ref "X3") (pin "GND@1") (pinfunction "GND1_GND@1") (pintype "power_in"))
      (node (ref "X3") (pin "GND@2") (pinfunction "GND2_GND@2") (pintype "power_in"))
      (node (ref "X3") (pin "GND@3") (pinfunction "GND3_GND@3") (pintype "power_in"))
      (node (ref "X3") (pin "GND@4") (pinfunction "GND4_GND@4") (pintype "power_in"))
      (node (ref "X31") (pin "P$6") (pinfunction "6_P$6") (pintype "passive"))
      (node (ref "X4") (pin "2") (pinfunction "K_2") (pintype "passive"))
      (node (ref "X5") (pin "GND@1") (pinfunction "GND1_GND@1") (pintype "power_in"))
      (node (ref "X5") (pin "GND@2") (pinfunction "GND2_GND@2") (pintype "power_in"))
      (node (ref "X5") (pin "GND@3") (pinfunction "GND3_GND@3") (pintype "power_in"))
      (node (ref "X5") (pin "GND@4") (pinfunction "GND4_GND@4") (pintype "power_in"))
      (node (ref "X8") (pin "GND@1") (pinfunction "GND1_GND@1") (pintype "power_in"))
      (node (ref "X8") (pin "GND@2") (pinfunction "GND2_GND@2") (pintype "power_in"))
      (node (ref "X8") (pin "GND@3") (pinfunction "GND3_GND@3") (pintype "power_in"))
      (node (ref "X8") (pin "GND@4") (pinfunction "GND4_GND@4") (pintype "power_in"))
    )
    (net (code "57") (name "IRQ-A") (class "Default")
      (node (ref "NRF24L01+") (pin "8") (pinfunction "IRQ_8") (pintype "bidirectional"))
      (node (ref "RS485") (pin "2") (pinfunction "~{RE}_2") (pintype "input"))
      (node (ref "RS485") (pin "3") (pinfunction "DE_3") (pintype "input"))
      (node (ref "U$2") (pin "D2") (pinfunction "D2_D2") (pintype "bidirectional"))
    )
    (net (code "58") (name "MOSI-A") (class "Default")
      (node (ref "NRF24L01+") (pin "6") (pinfunction "MOSI_6") (pintype "bidirectional"))
      (node (ref "U$2") (pin "D11") (pinfunction "D11_D11") (pintype "bidirectional"))
      (node (ref "X31") (pin "P$4") (pinfunction "4_P$4") (pintype "passive"))
    )
    (net (code "59") (name "Net-(C8-Pad1)") (class "Default")
      (node (ref "C8") (pin "1") (pinfunction "1_1") (pintype "passive"))
      (node (ref "R3") (pin "1") (pinfunction "1_1") (pintype "passive"))
      (node (ref "R5") (pin "1") (pinfunction "1_1") (pintype "passive"))
    )
    (net (code "60") (name "Net-(CHPD-Pad2)") (class "Default")
      (node (ref "CHPD") (pin "2") (pinfunction "2_2") (pintype "passive"))
      (node (ref "U$3") (pin "CH_PD") (pinfunction "CH_PD_CH_PD") (pintype "bidirectional"))
    )
    (net (code "61") (name "Net-(F1-2)") (class "Default")
      (node (ref "F1") (pin "P$2") (pinfunction "2_P$2") (pintype "passive"))
      (node (ref "X4") (pin "1") (pinfunction "K_1") (pintype "passive"))
    )
    (net (code "62") (name "Net-(IC31-AREF)") (class "Default")
      (node (ref "C32") (pin "1") (pinfunction "1_1") (pintype "passive"))
      (node (ref "IC31") (pin "20") (pinfunction "AREF_20") (pintype "bidirectional"))
    )
    (net (code "63") (name "Net-(IC31-PB6(XTAL1{slash}TOSC1))") (class "Default")
      (node (ref "C14") (pin "2") (pinfunction "2_2") (pintype "passive"))
      (node (ref "IC31") (pin "7") (pinfunction "PB6(XTAL1/TOSC1)_7") (pintype "bidirectional"))
      (node (ref "R4") (pin "2") (pinfunction "2_2") (pintype "passive"))
      (node (ref "Y2") (pin "P$2") (pinfunction "2_P$2") (pintype "passive"))
    )
    (net (code "64") (name "Net-(IC31-PB7(XTAL2{slash}TOSC2))") (class "Default")
      (node (ref "C15") (pin "2") (pinfunction "2_2") (pintype "passive"))
      (node (ref "IC31") (pin "8") (pinfunction "PB7(XTAL2/TOSC2)_8") (pintype "bidirectional"))
      (node (ref "R4") (pin "1") (pinfunction "1_1") (pintype "passive"))
      (node (ref "Y2") (pin "P$1") (pinfunction "1_P$1") (pintype "passive"))
    )
    (net (code "65") (name "Net-(L1-Pad1)") (class "Default")
      (node (ref "L1") (pin "1") (pinfunction "1_1") (pintype "passive"))
      (node (ref "U$2") (pin "VCC") (pinfunction "VCC_VCC") (pintype "bidirectional"))
    )
    (net (code "66") (name "Net-(LED-PadA)") (class "Default")
      (node (ref "LED") (pin "A") (pinfunction "A_A") (pintype "passive"))
      (node (ref "R32") (pin "2") (pinfunction "2_2") (pintype "passive"))
    )
    (net (code "67") (name "Net-(NRF24L01+-VCC)") (class "Default")
      (node (ref "C5") (pin "+") (pinfunction "+_+") (pintype "passive"))
      (node (ref "L1") (pin "2") (pinfunction "2_2") (pintype "passive"))
      (node (ref "NRF24L01+") (pin "2") (pinfunction "VCC_2") (pintype "power_in"))
    )
    (net (code "68") (name "Net-(PRG-Pad1)") (class "Default")
      (node (ref "PRG") (pin "1") (pinfunction "1_1") (pintype "passive"))
      (node (ref "U$3") (pin "GPIO0") (pinfunction "GPIO0_GPIO0") (pintype "bidirectional"))
    )
    (net (code "69") (name "Net-(U$3-RXD)") (class "Default")
      (node (ref "RX") (pin "2") (pinfunction "2_2") (pintype "passive"))
      (node (ref "U$3") (pin "RX") (pinfunction "RXD_RX") (pintype "bidirectional"))
    )
    (net (code "70") (name "Net-(U$3-TXD)") (class "Default")
      (node (ref "TX") (pin "2") (pinfunction "2_2") (pintype "passive"))
      (node (ref "U$3") (pin "TX") (pinfunction "TXD_TX") (pintype "bidirectional"))
    )
    (net (code "71") (name "Net-(X8-ANT)") (class "Default")
      (node (ref "ANT") (pin "1") (pinfunction "1_1") (pintype "passive"))
      (node (ref "U1") (pin "ANT") (pinfunction "ANT_ANT") (pintype "passive"))
      (node (ref "X8") (pin "P") (pinfunction "ANT_P") (pintype "bidirectional"))
    )
    (net (code "72") (name "R1-HM") (class "Default")
      (node (ref "HMMOD-UART") (pin "5") (pinfunction "TX_5") (pintype "bidirectional"))
      (node (ref "R1") (pin "3") (pinfunction "3_3") (pintype "passive"))
    )
    (net (code "73") (name "R1-MY") (class "Default")
      (node (ref "IC31") (pin "31") (pinfunction "PD1(TXD)_31") (pintype "bidirectional"))
      (node (ref "R1") (pin "1") (pinfunction "1_1") (pintype "passive"))
    )
    (net (code "74") (name "T1-HM") (class "Default")
      (node (ref "HMMOD-UART") (pin "6") (pinfunction "RX_6") (pintype "bidirectional"))
      (node (ref "T1") (pin "3") (pinfunction "3_3") (pintype "passive"))
    )
    (net (code "75") (name "T1-MY") (class "Default")
      (node (ref "IC31") (pin "30") (pinfunction "PD0(RXD)_30") (pintype "bidirectional"))
      (node (ref "T1") (pin "1") (pinfunction "1_1") (pintype "passive"))
    )
    (net (code "76") (name "VCC") (class "Default")
      (node (ref "3V3") (pin "1") (pinfunction "1_1") (pintype "passive"))
      (node (ref "C1") (pin "2") (pinfunction "2_2") (pintype "passive"))
      (node (ref "C11") (pin "2") (pinfunction "2_2") (pintype "passive"))
      (node (ref "C12") (pin "1") (pinfunction "1_1") (pintype "passive"))
      (node (ref "C2") (pin "2") (pinfunction "2_2") (pintype "passive"))
      (node (ref "C3") (pin "2") (pinfunction "2_2") (pintype "passive"))
      (node (ref "C31") (pin "1") (pinfunction "1_1") (pintype "passive"))
      (node (ref "C4") (pin "2") (pinfunction "2_2") (pintype "passive"))
      (node (ref "C6") (pin "1") (pinfunction "1_1") (pintype "passive"))
      (node (ref "CC0") (pin "VCC") (pinfunction "VCC_VCC") (pintype "power_in"))
      (node (ref "CC1") (pin "VCC") (pinfunction "VCC_VCC") (pintype "power_in"))
      (node (ref "CC2") (pin "VCC") (pinfunction "VCC_VCC") (pintype "power_in"))
      (node (ref "CC2-EXT") (pin "VCC@0") (pinfunction "VCC_VCC@0") (pintype "power_in"))
      (node (ref "CC2-EXT") (pin "VCC@1") (pinfunction "VCC_VCC@1") (pintype "power_in"))
      (node (ref "CC3") (pin "VCC") (pinfunction "VCC_VCC") (pintype "power_in"))
      (node (ref "CC3-EXT") (pin "VCC@0") (pinfunction "VCC_VCC@0") (pintype "power_in"))
      (node (ref "CC3-EXT") (pin "VCC@1") (pinfunction "VCC_VCC@1") (pintype "power_in"))
      (node (ref "CHPD") (pin "1") (pinfunction "1_1") (pintype "passive"))
      (node (ref "DBG") (pin "1") (pinfunction "1_1") (pintype "passive"))
      (node (ref "HMMOD-UART") (pin "1") (pinfunction "VCC_1") (pintype "power_in"))
      (node (ref "IC2") (pin "10") (pinfunction "V+_10") (pintype "power_in"))
      (node (ref "IC2") (pin "11") (pinfunction "V+_11") (pintype "power_in"))
      (node (ref "IC31") (pin "18") (pinfunction "AVCC_18") (pintype "bidirectional"))
      (node (ref "IC31") (pin "4") (pinfunction "VCC_4") (pintype "bidirectional"))
      (node (ref "IC31") (pin "6") (pinfunction "VCC_6") (pintype "bidirectional"))
      (node (ref "R2") (pin "2") (pinfunction "2_2") (pintype "passive"))
      (node (ref "R34") (pin "1") (pinfunction "1_1") (pintype "passive"))
      (node (ref "RADIO0B") (pin "VCC") (pinfunction "VCC_VCC") (pintype "power_in"))
      (node (ref "RADIO1B") (pin "VCC") (pinfunction "VCC_VCC") (pintype "power_in"))
      (node (ref "RADIO2B") (pin "VCC") (pinfunction "VCC_VCC") (pintype "power_in"))
      (node (ref "RADIO3B") (pin "VCC") (pinfunction "VCC_VCC") (pintype "power_in"))
      (node (ref "U$1") (pin "1") (pinfunction "VCC_1") (pintype "bidirectional"))
      (node (ref "U$1") (pin "40") (pinfunction "AV+_40") (pintype "bidirectional"))
      (node (ref "U$3") (pin "VCC") (pinfunction "VCC_VCC") (pintype "bidirectional"))
      (node (ref "U1") (pin "3.3V") (pinfunction "3.3V_3.3V") (pintype "power_in"))
      (node (ref "UART0") (pin "1") (pinfunction "1_1") (pintype "passive"))
      (node (ref "UART1") (pin "1") (pinfunction "1_1") (pintype "passive"))
      (node (ref "X31") (pin "P$2") (pinfunction "2_P$2") (pintype "passive"))
    )
    (net (code "77") (name "unconnected-(CC3-EXT-PadGDO0)") (class "Default")
      (node (ref "CC3-EXT") (pin "GDO0") (pinfunction "GDO0_GDO0") (pintype "bidirectional"))
    )
    (net (code "78") (name "unconnected-(HMMOD-UART-C2D-Pad3)") (class "Default")
      (node (ref "HMMOD-UART") (pin "3") (pinfunction "C2D_3") (pintype "bidirectional"))
    )
    (net (code "79") (name "unconnected-(HMMOD-UART-\\~{RESET}-Pad4)") (class "Default")
      (node (ref "HMMOD-UART") (pin "4") (pinfunction "\\~{RESET}_4") (pintype "bidirectional"))
    )
    (net (code "80") (name "unconnected-(IC2-NC-Pad9)") (class "Default")
      (node (ref "IC2") (pin "9") (pinfunction "NC_9") (pintype "no_connect"))
    )
    (net (code "81") (name "unconnected-(IC31-ADC6-Pad19)") (class "Default")
      (node (ref "IC31") (pin "19") (pinfunction "ADC6_19") (pintype "bidirectional"))
    )
    (net (code "82") (name "unconnected-(IC31-ADC7-Pad22)") (class "Default")
      (node (ref "IC31") (pin "22") (pinfunction "ADC7_22") (pintype "bidirectional"))
    )
    (net (code "83") (name "unconnected-(IC31-PB0(ICP)-Pad12)") (class "Default")
      (node (ref "IC31") (pin "12") (pinfunction "PB0(ICP)_12") (pintype "bidirectional"))
    )
    (net (code "84") (name "unconnected-(IC31-PC0(ADC0)-Pad23)") (class "Default")
      (node (ref "IC31") (pin "23") (pinfunction "PC0(ADC0)_23") (pintype "bidirectional"))
    )
    (net (code "85") (name "unconnected-(IC31-PC1(ADC1)-Pad24)") (class "Default")
      (node (ref "IC31") (pin "24") (pinfunction "PC1(ADC1)_24") (pintype "bidirectional"))
    )
    (net (code "86") (name "unconnected-(IC31-PC2(ADC2)-Pad25)") (class "Default")
      (node (ref "IC31") (pin "25") (pinfunction "PC2(ADC2)_25") (pintype "bidirectional"))
    )
    (net (code "87") (name "unconnected-(IC31-PC3(ADC3)-Pad26)") (class "Default")
      (node (ref "IC31") (pin "26") (pinfunction "PC3(ADC3)_26") (pintype "bidirectional"))
    )
    (net (code "88") (name "unconnected-(IC31-PC4(ADC4{slash}SDA)-Pad27)") (class "Default")
      (node (ref "IC31") (pin "27") (pinfunction "PC4(ADC4/SDA)_27") (pintype "bidirectional"))
    )
    (net (code "89") (name "unconnected-(IC31-PC5(ADC5{slash}SCL)-Pad28)") (class "Default")
      (node (ref "IC31") (pin "28") (pinfunction "PC5(ADC5/SCL)_28") (pintype "bidirectional"))
    )
    (net (code "90") (name "unconnected-(IC31-PD3(INT1)-Pad1)") (class "Default")
      (node (ref "IC31") (pin "1") (pinfunction "PD3(INT1)_1") (pintype "bidirectional"))
    )
    (net (code "91") (name "unconnected-(IC31-PD5(T1)-Pad9)") (class "Default")
      (node (ref "IC31") (pin "9") (pinfunction "PD5(T1)_9") (pintype "bidirectional"))
    )
    (net (code "92") (name "unconnected-(IC31-PD6(AIN0)-Pad10)") (class "Default")
      (node (ref "IC31") (pin "10") (pinfunction "PD6(AIN0)_10") (pintype "bidirectional"))
    )
    (net (code "93") (name "unconnected-(IC31-PD7(AIN1)-Pad11)") (class "Default")
      (node (ref "IC31") (pin "11") (pinfunction "PD7(AIN1)_11") (pintype "bidirectional"))
    )
    (net (code "94") (name "unconnected-(U$1-23{slash}USB_DP-Pad12)") (class "Default")
      (node (ref "U$1") (pin "12") (pinfunction "23/USB_DP_12") (pintype "bidirectional"))
    )
    (net (code "95") (name "unconnected-(U$1-24{slash}USB_DM-Pad13)") (class "Default")
      (node (ref "U$1") (pin "13") (pinfunction "24/USB_DM_13") (pintype "bidirectional"))
    )
    (net (code "96") (name "unconnected-(U$1-BUT-Pad3)") (class "Default")
      (node (ref "U$1") (pin "3") (pinfunction "BUT_3") (pintype "bidirectional"))
    )
    (net (code "97") (name "unconnected-(U$1-VBAT-Pad38)") (class "Default")
      (node (ref "U$1") (pin "38") (pinfunction "VBAT_38") (pintype "bidirectional"))
    )
    (net (code "98") (name "unconnected-(U$2-GND1-PadGND4)") (class "Default")
      (node (ref "U$2") (pin "GND4") (pinfunction "GND1_GND4") (pintype "bidirectional"))
    )
    (net (code "99") (name "unconnected-(U$2-GND2-PadGND1)") (class "Default")
      (node (ref "U$2") (pin "GND1") (pinfunction "GND2_GND1") (pintype "bidirectional"))
    )
    (net (code "100") (name "unconnected-(U$2-GND3-PadGND2)") (class "Default")
      (node (ref "U$2") (pin "GND2") (pinfunction "GND3_GND2") (pintype "bidirectional"))
    )
    (net (code "101") (name "unconnected-(U$2-GND4-PadGND3)") (class "Default")
      (node (ref "U$2") (pin "GND3") (pinfunction "GND4_GND3") (pintype "bidirectional"))
    )
    (net (code "102") (name "unconnected-(U$2-PadA0)") (class "Default")
      (node (ref "U$2") (pin "A0") (pinfunction "A0_A0") (pintype "bidirectional"))
    )
    (net (code "103") (name "unconnected-(U$2-PadA1)") (class "Default")
      (node (ref "U$2") (pin "A1") (pinfunction "A1_A1") (pintype "bidirectional"))
    )
    (net (code "104") (name "unconnected-(U$2-PadA2)") (class "Default")
      (node (ref "U$2") (pin "A2") (pinfunction "A2_A2") (pintype "bidirectional"))
    )
    (net (code "105") (name "unconnected-(U$2-PadA3)") (class "Default")
      (node (ref "U$2") (pin "A3") (pinfunction "A3_A3") (pintype "bidirectional"))
    )
    (net (code "106") (name "unconnected-(U$2-PadA4)") (class "Default")
      (node (ref "U$2") (pin "A4") (pinfunction "A4_A4") (pintype "bidirectional"))
    )
    (net (code "107") (name "unconnected-(U$2-PadA5)") (class "Default")
      (node (ref "U$2") (pin "A5") (pinfunction "A5_A5") (pintype "bidirectional"))
    )
    (net (code "108") (name "unconnected-(U$2-PadA6)") (class "Default")
      (node (ref "U$2") (pin "A6") (pinfunction "A6_A6") (pintype "bidirectional"))
    )
    (net (code "109") (name "unconnected-(U$2-PadA7)") (class "Default")
      (node (ref "U$2") (pin "A7") (pinfunction "A7_A7") (pintype "bidirectional"))
    )
    (net (code "110") (name "unconnected-(U$2-PadD3)") (class "Default")
      (node (ref "U$2") (pin "D3") (pinfunction "D3_D3") (pintype "bidirectional"))
    )
    (net (code "111") (name "unconnected-(U$2-PadD4)") (class "Default")
      (node (ref "U$2") (pin "D4") (pinfunction "D4_D4") (pintype "bidirectional"))
    )
    (net (code "112") (name "unconnected-(U$2-PadD5)") (class "Default")
      (node (ref "U$2") (pin "D5") (pinfunction "D5_D5") (pintype "bidirectional"))
    )
    (net (code "113") (name "unconnected-(U$2-PadD6)") (class "Default")
      (node (ref "U$2") (pin "D6") (pinfunction "D6_D6") (pintype "bidirectional"))
    )
    (net (code "114") (name "unconnected-(U$2-PadD7)") (class "Default")
      (node (ref "U$2") (pin "D7") (pinfunction "D7_D7") (pintype "bidirectional"))
    )
    (net (code "115") (name "unconnected-(U$2-PadDTR)") (class "Default")
      (node (ref "U$2") (pin "DTR") (pinfunction "DTR_DTR") (pintype "bidirectional"))
    )
    (net (code "116") (name "unconnected-(U$2-PadRAW)") (class "Default")
      (node (ref "U$2") (pin "RAW") (pinfunction "RAW_RAW") (pintype "bidirectional"))
    )
    (net (code "117") (name "unconnected-(U$2-PadRST)") (class "Default")
      (node (ref "U$2") (pin "RST") (pinfunction "RST_RST") (pintype "bidirectional"))
    )
    (net (code "118") (name "unconnected-(U$2-PadRST1)") (class "Default")
      (node (ref "U$2") (pin "RST1") (pinfunction "RST1_RST1") (pintype "bidirectional"))
    )
    (net (code "119") (name "unconnected-(U$2-PadRX1-1)") (class "Default")
      (node (ref "U$2") (pin "RX1-1") (pinfunction "RX1-1_RX1-1") (pintype "bidirectional"))
    )
    (net (code "120") (name "unconnected-(U$2-PadTX0-1)") (class "Default")
      (node (ref "U$2") (pin "TX0-1") (pinfunction "TX0-1_TX0-1") (pintype "bidirectional"))
    )
    (net (code "121") (name "unconnected-(U$2-PadVCC1)") (class "Default")
      (node (ref "U$2") (pin "VCC1") (pinfunction "VCC1_VCC1") (pintype "bidirectional"))
    )
    (net (code "122") (name "unconnected-(U$3-PadGPIO2)") (class "Default")
      (node (ref "U$3") (pin "GPIO2") (pinfunction "GPIO2_GPIO2") (pintype "bidirectional"))
    )
    (net (code "123") (name "unconnected-(U$3-PadRST)") (class "Default")
      (node (ref "U$3") (pin "RST") (pinfunction "RST_RST") (pintype "bidirectional"))
    )
    (net (code "124") (name "unconnected-(U1-PadDIO1)") (class "Default")
      (node (ref "U1") (pin "DIO1") (pinfunction "DIO1_DIO1") (pintype "bidirectional"))
    )
    (net (code "125") (name "unconnected-(U1-PadDIO2)") (class "Default")
      (node (ref "U1") (pin "DIO2") (pinfunction "DIO2_DIO2") (pintype "bidirectional"))
    )
    (net (code "126") (name "unconnected-(U1-PadRESET)") (class "Default")
      (node (ref "U1") (pin "RESET") (pinfunction "RESET_RESET") (pintype "input"))
    )
  )
)
